# Peripherals.net
KiCad netlist of a schematic drawn in Altium Designer
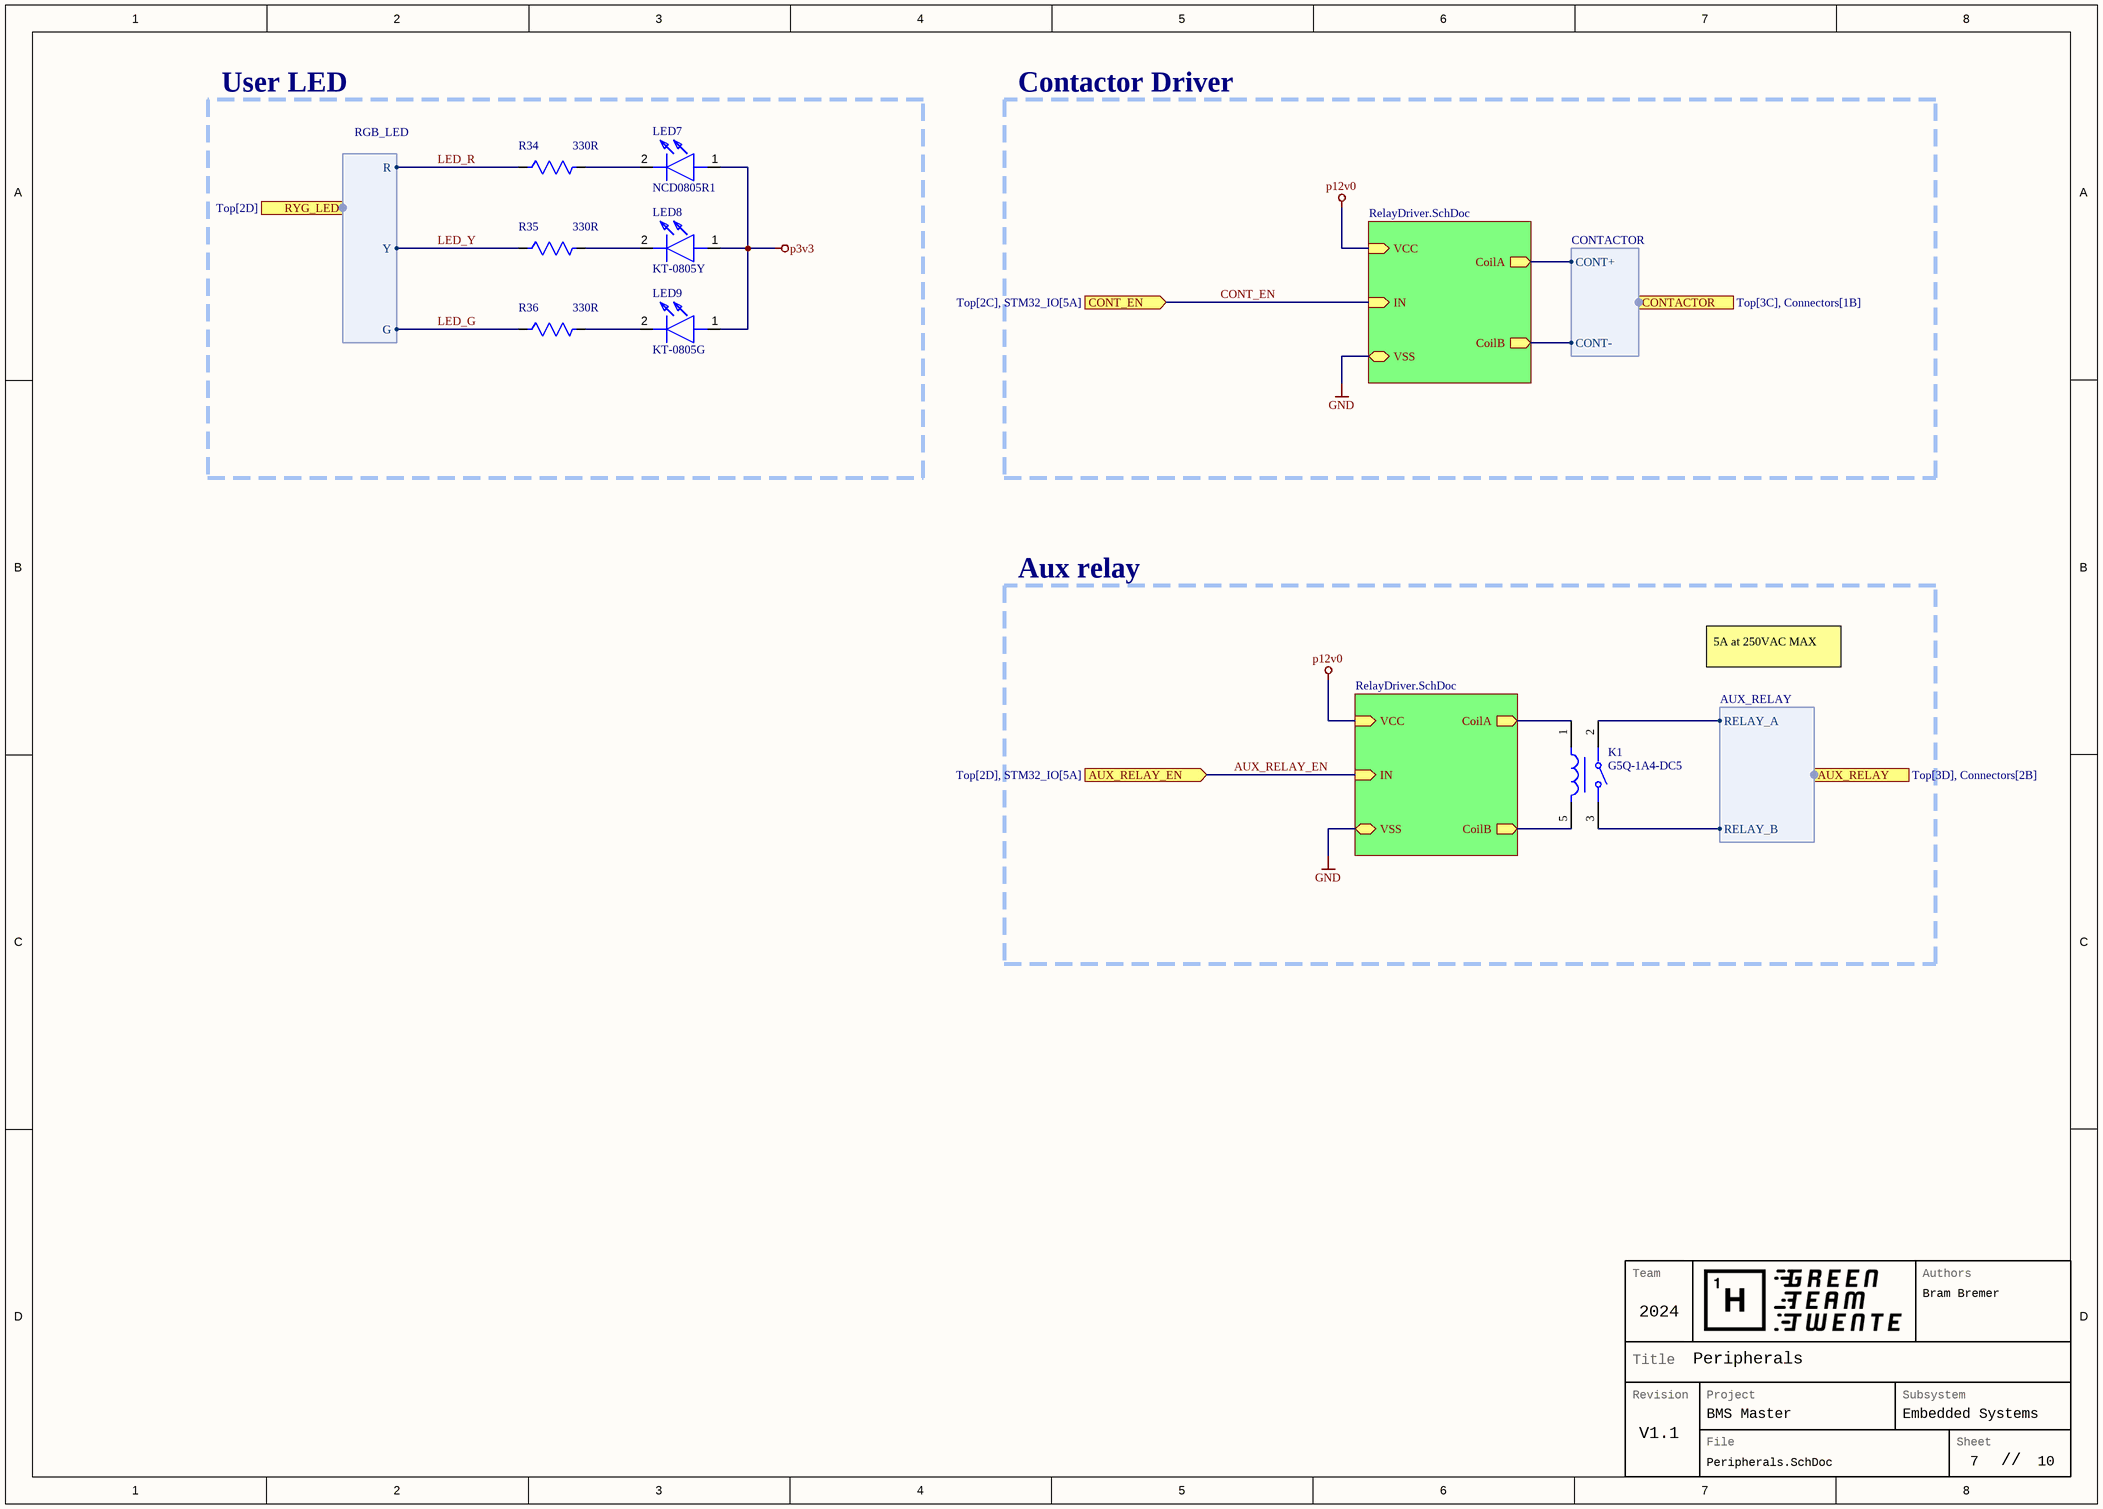
[diagram p0: Peripherals.SchDoc]

(export (version "E")
  (design (tool "Eeschema 10.0.6"))
  (components
    (comp (ref "K1")
      (value "G5Q-1A4-DC5")
      (footprint "FP-G5Q-1A4-DC5-MFG")
      (description "RELAY GEN PURPOSE SPST 10A 5V")
      (libsource (lib "Altium Content Vault") (part "a4f01a0af5cf5a11a224c07dc72907a"))
    )
    (comp (ref "LED7")
      (value "NCD0805R1")
      (footprint "KT0805G")
      (description "LED")
      (fields (field (name "MANUFACTURER_PART_NUMBER") "KT-0805G") (field (name "JLCPCB PART #") "C84256"))
      (libsource (lib "FlexBMS_lib") (part "KT-0805G"))
    )
    (comp (ref "LED8")
      (value "KT-0805Y")
      (footprint "KT0805G")
      (description "LED")
      (fields (field (name "MANUFACTURER_PART_NUMBER") "KT-0805G") (field (name "JLCPCB PART #") "C2296"))
      (libsource (lib "FlexBMS_lib") (part "KT-0805G"))
    )
    (comp (ref "LED9")
      (value "KT-0805G")
      (footprint "KT0805G")
      (description "LED")
      (fields (field (name "JLCPCB PART #") "C2297"))
      (libsource (lib "FlexBMS_lib") (part "KT-0805G"))
    )
    (comp (ref "R34")
      (value "330R")
      (footprint "RES_SM0603_YAGEORC_N")
      (description "GTT Standard 0603 Resistor")
      (fields (field (name "POWER") "62.5mW") (field (name "TOLERANCE") "1%"))
      (libsource (lib "Green Team Twente") (part "RES_GENERIC"))
    )
    (comp (ref "R35")
      (value "330R")
      (footprint "RES_SM0603_YAGEORC_N")
      (description "GTT Standard 0603 Resistor")
      (fields (field (name "POWER") "62.5mW") (field (name "TOLERANCE") "1%"))
      (libsource (lib "Green Team Twente") (part "RES_GENERIC"))
    )
    (comp (ref "R36")
      (value "330R")
      (footprint "RES_SM0603_YAGEORC_N")
      (description "GTT Standard 0603 Resistor")
      (fields (field (name "POWER") "62.5mW") (field (name "TOLERANCE") "1%"))
      (libsource (lib "Green Team Twente") (part "RES_GENERIC"))
    )
  )
  (nets
    (net (code "7") (name "/CoilA_1") (class "Default")
      (node (ref "K1") (pin "1") (pinfunction "1_1") (pintype "passive"))
    )
    (net (code "9") (name "/CoilB_1") (class "Default")
      (node (ref "K1") (pin "5") (pinfunction "5_5") (pintype "passive"))
    )
    (net (code "10") (name "/LED_G") (class "Default")
      (node (ref "R36") (pin "1") (pinfunction "1_1") (pintype "passive"))
    )
    (net (code "11") (name "/LED_R") (class "Default")
      (node (ref "R34") (pin "1") (pinfunction "1_1") (pintype "passive"))
    )
    (net (code "12") (name "/LED_Y") (class "Default")
      (node (ref "R35") (pin "1") (pinfunction "1_1") (pintype "passive"))
    )
    (net (code "17") (name "Net-(LED7-K)") (class "Default")
      (node (ref "LED7") (pin "2") (pinfunction "K_2") (pintype "passive"))
      (node (ref "R34") (pin "2") (pinfunction "2_2") (pintype "passive"))
    )
    (net (code "18") (name "Net-(LED8-K)") (class "Default")
      (node (ref "LED8") (pin "2") (pinfunction "K_2") (pintype "passive"))
      (node (ref "R35") (pin "2") (pinfunction "2_2") (pintype "passive"))
    )
    (net (code "19") (name "Net-(LED9-K)") (class "Default")
      (node (ref "LED9") (pin "2") (pinfunction "K_2") (pintype "passive"))
      (node (ref "R36") (pin "2") (pinfunction "2_2") (pintype "passive"))
    )
    (net (code "20") (name "p3v3") (class "Default")
      (node (ref "LED7") (pin "1") (pinfunction "A_1") (pintype "passive"))
      (node (ref "LED8") (pin "1") (pinfunction "A_1") (pintype "passive"))
      (node (ref "LED9") (pin "1") (pinfunction "A_1") (pintype "passive"))
    )
    (net (code "22") (name "unconnected-(K1-Pad2)") (class "Default")
      (node (ref "K1") (pin "2") (pinfunction "2_2") (pintype "passive"))
    )
    (net (code "23") (name "unconnected-(K1-Pad3)") (class "Default")
      (node (ref "K1") (pin "3") (pinfunction "3_3") (pintype "passive"))
    )
  )
)
